# NFC.net
KiCad netlist of a schematic drawn in Altium Designer
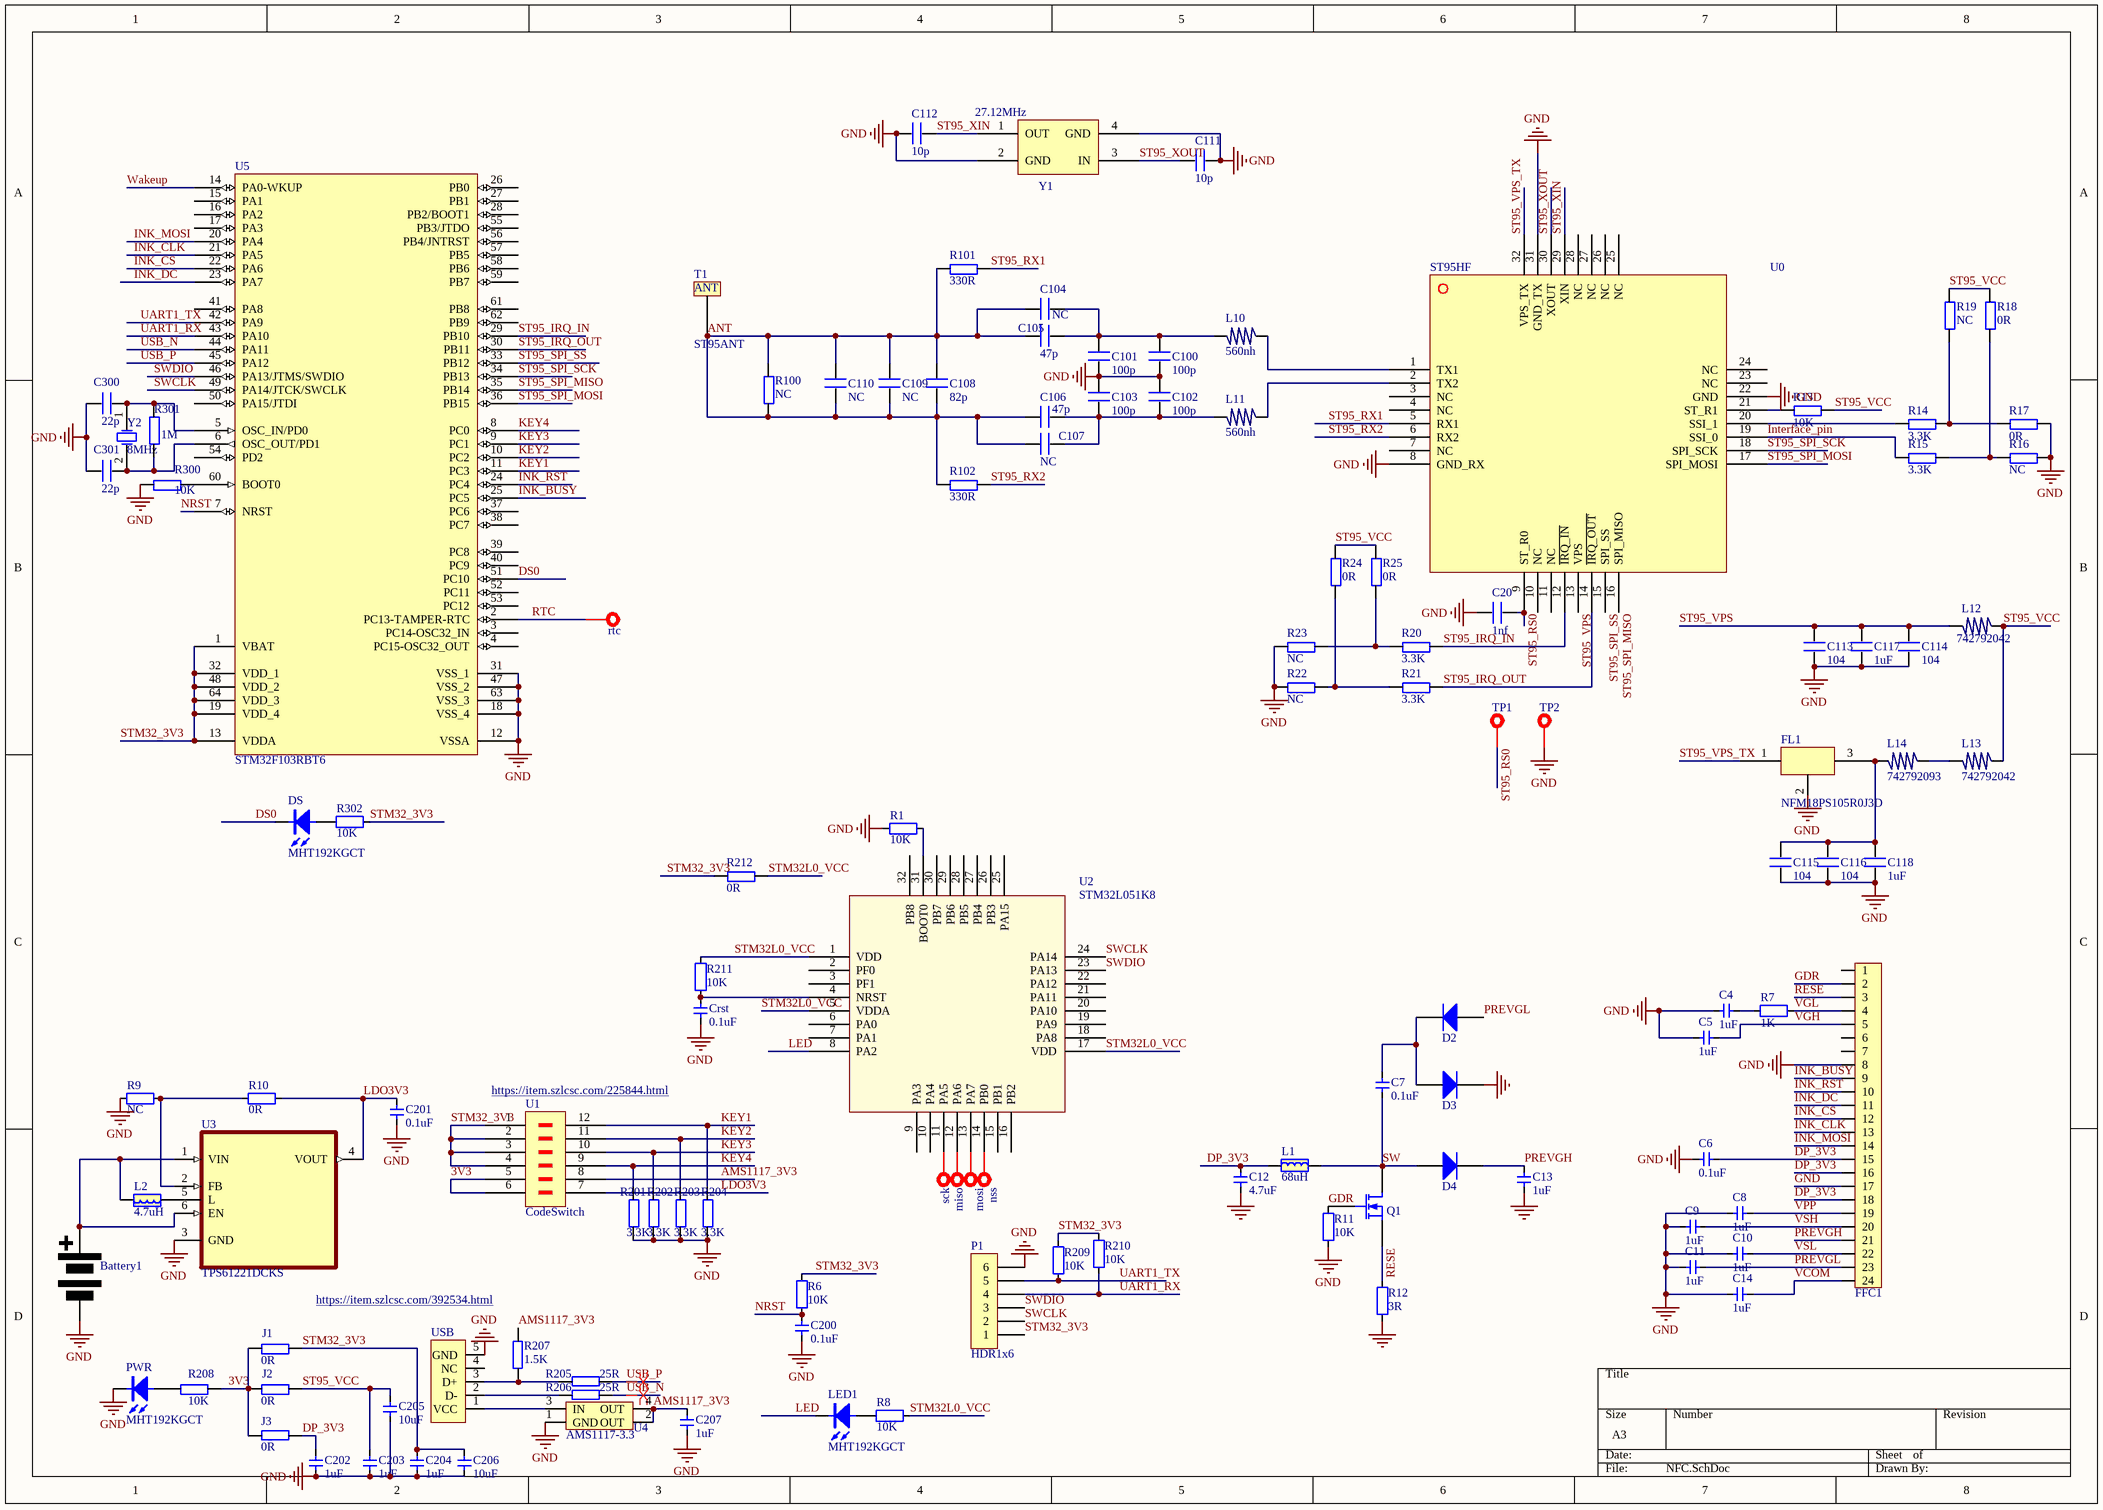
[diagram p0: NFC.SchDoc]

(export (version "E")
  (design (tool "Eeschema 10.0.6"))
  (components
    (comp (ref "Battery1")
      (value "Battery")
      (footprint "CR2032-1")
      (libsource (lib "KitSprout") (part "Battery"))
    )
    (comp (ref "C4")
      (value "1uF")
      (footprint "0402cap")
      (description "Capacitor")
      (libsource (lib "MyPcbLib") (part "电容-0402"))
    )
    (comp (ref "C5")
      (value "1uF")
      (footprint "0402cap")
      (description "Capacitor")
      (libsource (lib "MyPcbLib") (part "电容-0402"))
    )
    (comp (ref "C6")
      (value "0.1uF")
      (footprint "0402cap")
      (description "Capacitor")
      (libsource (lib "MyPcbLib") (part "电容-0402"))
    )
    (comp (ref "C7")
      (value "0.1uF")
      (footprint "0402cap")
      (description "Capacitor")
      (libsource (lib "MyPcbLib") (part "电容-0402"))
    )
    (comp (ref "C8")
      (value "1uF")
      (footprint "0402cap")
      (description "Capacitor")
      (libsource (lib "MyPcbLib") (part "电容-0402"))
    )
    (comp (ref "C9")
      (value "1uF")
      (footprint "0402cap")
      (description "Capacitor")
      (libsource (lib "MyPcbLib") (part "电容-0402"))
    )
    (comp (ref "C10")
      (value "1uF")
      (footprint "0402cap")
      (description "Capacitor")
      (libsource (lib "MyPcbLib") (part "电容-0402"))
    )
    (comp (ref "C11")
      (value "1uF")
      (footprint "0402cap")
      (description "Capacitor")
      (libsource (lib "MyPcbLib") (part "电容-0402"))
    )
    (comp (ref "C12")
      (value "4.7uF")
      (footprint "0402cap")
      (description "Capacitor")
      (libsource (lib "MyPcbLib") (part "电容-0603"))
    )
    (comp (ref "C13")
      (value "1uF")
      (footprint "0402cap")
      (description "Capacitor")
      (libsource (lib "MyPcbLib") (part "电容-0402"))
    )
    (comp (ref "C14")
      (value "1uF")
      (footprint "0402cap")
      (description "Capacitor")
      (libsource (lib "MyPcbLib") (part "电容-0402"))
    )
    (comp (ref "C20") (value "1nf") (footprint "0402cap") (libsource (lib "WARSHIP") (part "C")))
    (comp (ref "C100") (value "100p") (footprint "0603P") (libsource (lib "WARSHIP") (part "C")))
    (comp (ref "C101") (value "100p") (footprint "0603P") (libsource (lib "WARSHIP") (part "C")))
    (comp (ref "C102") (value "100p") (footprint "0603P") (libsource (lib "WARSHIP") (part "C")))
    (comp (ref "C103") (value "100p") (footprint "0603P") (libsource (lib "WARSHIP") (part "C")))
    (comp (ref "C104") (value "NC") (footprint "0603P") (libsource (lib "WARSHIP") (part "C")))
    (comp (ref "C105") (value "47p") (footprint "0603P") (libsource (lib "WARSHIP") (part "C")))
    (comp (ref "C106") (value "47p") (footprint "0603P") (libsource (lib "WARSHIP") (part "C")))
    (comp (ref "C107") (value "NC") (footprint "0603P") (libsource (lib "WARSHIP") (part "C")))
    (comp (ref "C108") (value "82p") (footprint "0603P") (libsource (lib "WARSHIP") (part "C")))
    (comp (ref "C109") (value "NC") (footprint "0603P") (libsource (lib "WARSHIP") (part "C")))
    (comp (ref "C110") (value "NC") (footprint "0603P") (libsource (lib "WARSHIP") (part "C")))
    (comp (ref "C111") (value "10p") (footprint "0402cap") (libsource (lib "WARSHIP") (part "C")))
    (comp (ref "C112") (value "10p") (footprint "0402cap") (libsource (lib "WARSHIP") (part "C")))
    (comp (ref "C113") (value "104") (footprint "0402cap") (libsource (lib "WARSHIP") (part "C")))
    (comp (ref "C114") (value "104") (footprint "0402cap") (libsource (lib "WARSHIP") (part "C")))
    (comp (ref "C115") (value "104") (footprint "0402cap") (libsource (lib "WARSHIP") (part "C")))
    (comp (ref "C116") (value "104") (footprint "0402cap") (libsource (lib "WARSHIP") (part "C")))
    (comp (ref "C117") (value "1uF") (footprint "0402cap") (libsource (lib "WARSHIP") (part "C")))
    (comp (ref "C118") (value "1uF") (footprint "0402cap") (libsource (lib "WARSHIP") (part "C")))
    (comp (ref "C200")
      (value "0.1uF")
      (footprint "0402cap")
      (description "Capacitor")
      (libsource (lib "MyPcbLib") (part "电容-0402"))
    )
    (comp (ref "C201")
      (value "0.1uF")
      (footprint "0402cap")
      (description "Capacitor")
      (libsource (lib "MyPcbLib") (part "电容-0402"))
    )
    (comp (ref "C202")
      (value "1uF")
      (footprint "0402cap")
      (description "Capacitor")
      (libsource (lib "MyPcbLib") (part "电容-0402"))
    )
    (comp (ref "C203")
      (value "1uF")
      (footprint "0402cap")
      (description "Capacitor")
      (libsource (lib "MyPcbLib") (part "电容-0402"))
    )
    (comp (ref "C204")
      (value "1uF")
      (footprint "0402cap")
      (description "Capacitor")
      (libsource (lib "MyPcbLib") (part "电容-0402"))
    )
    (comp (ref "C205")
      (value "10uF")
      (footprint "0603p")
      (description "Capacitor")
      (libsource (lib "MyPcbLib") (part "电容-0402"))
    )
    (comp (ref "C206")
      (value "10uF")
      (footprint "0603p")
      (description "Capacitor")
      (libsource (lib "MyPcbLib") (part "电容-0402"))
    )
    (comp (ref "C207")
      (value "1uF")
      (footprint "0402cap")
      (description "Capacitor")
      (libsource (lib "MyPcbLib") (part "电容-0402"))
    )
    (comp (ref "C300") (value "22p") (footprint "0402cap") (libsource (lib "WARSHIP") (part "C")))
    (comp (ref "C301") (value "22p") (footprint "0402cap") (libsource (lib "WARSHIP") (part "C")))
    (comp (ref "Crst")
      (value "0.1uF")
      (footprint "0402cap")
      (description "Capacitor")
      (libsource (lib "MyPcbLib") (part "电容-0402"))
    )
    (comp (ref "D2")
      (value "二极管-5819W")
      (footprint "SOD-123")
      (description "40V")
      (libsource (lib "MyPcbLib") (part "二极管-5819W"))
    )
    (comp (ref "D3")
      (value "二极管-5819W")
      (footprint "SOD-123")
      (description "40V")
      (libsource (lib "MyPcbLib") (part "二极管-5819W"))
    )
    (comp (ref "D4")
      (value "二极管-5819W")
      (footprint "SOD-123")
      (description "40V")
      (libsource (lib "MyPcbLib") (part "二极管-5819W"))
    )
    (comp (ref "DS")
      (value "MHT192KGCT")
      (footprint "LED-0603")
      (description "LED")
      (libsource (lib "General") (part "LED"))
    )
    (comp (ref "FFC1")
      (value "FFC_0.5_24")
      (footprint "FFC_0.5_24_INK")
      (description "FFC")
      (libsource (lib "MyPcbLib") (part "FFC_0.5_24_INK"))
    )
    (comp (ref "FL1")
      (value "NFM18PS105R0J3D")
      (footprint "NFM18PS")
      (libsource (lib "NFM18PS105R0J3D") (part "NFM18PS"))
    )
    (comp (ref "J1") (value "0R") (footprint "res0402") (libsource (lib "WARSHIP") (part "R")))
    (comp (ref "J2") (value "0R") (footprint "res0402") (libsource (lib "WARSHIP") (part "R")))
    (comp (ref "J3") (value "0R") (footprint "res0402") (libsource (lib "WARSHIP") (part "R")))
    (comp (ref "L1")
      (value "68uH")
      (footprint "2520-L")
      (description "磁珠")
      (libsource (lib "MyPcbLib") (part "电感-2520"))
    )
    (comp (ref "L2")
      (value "4.7uH")
      (footprint "0805-L")
      (description "磁珠")
      (libsource (lib "MyPcbLib") (part "电感-0805"))
    )
    (comp (ref "L10") (value "560nh") (footprint "0805") (libsource (lib "WARSHIP") (part "L")))
    (comp (ref "L11") (value "560nh") (footprint "0805") (libsource (lib "WARSHIP") (part "L")))
    (comp (ref "L12") (value "742792042") (footprint "0805") (libsource (lib "WARSHIP") (part "L")))
    (comp (ref "L13") (value "742792042") (footprint "0805") (libsource (lib "WARSHIP") (part "L")))
    (comp (ref "L14") (value "742792093") (footprint "0805") (libsource (lib "WARSHIP") (part "L")))
    (comp (ref "LED1")
      (value "MHT192KGCT")
      (footprint "LED-0603")
      (description "LED")
      (libsource (lib "General") (part "LED"))
    )
    (comp (ref "miso")
      (value "TestPoint")
      (footprint "TestPoint")
      (libsource (lib "TestPoint") (part "TestPoint"))
    )
    (comp (ref "mosi")
      (value "TestPoint")
      (footprint "TestPoint")
      (libsource (lib "TestPoint") (part "TestPoint"))
    )
    (comp (ref "nss")
      (value "TestPoint")
      (footprint "TestPoint")
      (libsource (lib "TestPoint") (part "TestPoint"))
    )
    (comp (ref "P1")
      (value "HDR1x6")
      (footprint "PIN-6-2.54-1.0")
      (description "Connector")
      (libsource (lib "General") (part "HDR1x6"))
    )
    (comp (ref "PWR")
      (value "MHT192KGCT")
      (footprint "LED-0603")
      (description "LED")
      (libsource (lib "General") (part "LED"))
    )
    (comp (ref "Q1")
      (value "MOSFET-N")
      (footprint "SOT23-3")
      (description "N-Channel MOSFET")
      (fields (field (name "PUBLISHER") "Altium Limited"))
      (libsource (lib "MyPcbLib") (part "MOSFET-N"))
    )
    (comp (ref "R1")
      (value "10K")
      (footprint "res0402")
      (description "Resistor")
      (libsource (lib "") (part "电阻-0402_2"))
    )
    (comp (ref "R6")
      (value "10K")
      (footprint "res0402")
      (description "Resistor")
      (libsource (lib "MyPcbLib") (part "电阻-0402"))
    )
    (comp (ref "R7")
      (value "1K")
      (footprint "res0402")
      (description "Resistor")
      (libsource (lib "") (part "电阻-0402_2"))
    )
    (comp (ref "R8")
      (value "10K")
      (footprint "res0402")
      (description "Resistor")
      (libsource (lib "") (part "电阻-0402_1"))
    )
    (comp (ref "R9")
      (value "NC")
      (footprint "res0402")
      (description "Resistor")
      (libsource (lib "") (part "电阻-0402_2"))
    )
    (comp (ref "R10")
      (value "0R")
      (footprint "res0402")
      (description "Resistor")
      (libsource (lib "") (part "电阻-0402_2"))
    )
    (comp (ref "R11")
      (value "10K")
      (footprint "res0402")
      (description "Resistor")
      (libsource (lib "MyPcbLib") (part "电阻-0402"))
    )
    (comp (ref "R12")
      (value "3R")
      (footprint "res0402")
      (description "Resistor")
      (libsource (lib "MyPcbLib") (part "电阻-0402"))
    )
    (comp (ref "R13") (value "10K") (footprint "res0402") (libsource (lib "WARSHIP") (part "R")))
    (comp (ref "R14") (value "3.3K") (footprint "res0402") (libsource (lib "WARSHIP") (part "R")))
    (comp (ref "R15") (value "3.3K") (footprint "res0402") (libsource (lib "WARSHIP") (part "R")))
    (comp (ref "R16") (value "NC") (footprint "res0402") (libsource (lib "WARSHIP") (part "R")))
    (comp (ref "R17") (value "0R") (footprint "res0402") (libsource (lib "WARSHIP") (part "R")))
    (comp (ref "R18") (value "0R") (footprint "res0402") (libsource (lib "WARSHIP") (part "R")))
    (comp (ref "R19") (value "NC") (footprint "res0402") (libsource (lib "WARSHIP") (part "R")))
    (comp (ref "R20") (value "3.3K") (footprint "res0402") (libsource (lib "WARSHIP") (part "R")))
    (comp (ref "R21") (value "3.3K") (footprint "res0402") (libsource (lib "WARSHIP") (part "R")))
    (comp (ref "R22") (value "NC") (footprint "res0402") (libsource (lib "WARSHIP") (part "R")))
    (comp (ref "R23") (value "NC") (footprint "res0402") (libsource (lib "WARSHIP") (part "R")))
    (comp (ref "R24") (value "0R") (footprint "res0402") (libsource (lib "WARSHIP") (part "R")))
    (comp (ref "R25") (value "0R") (footprint "res0402") (libsource (lib "WARSHIP") (part "R")))
    (comp (ref "R100") (value "NC") (footprint "0603R") (libsource (lib "WARSHIP") (part "R")))
    (comp (ref "R101") (value "330R") (footprint "0603R") (libsource (lib "WARSHIP") (part "R")))
    (comp (ref "R102") (value "330R") (footprint "0603R") (libsource (lib "WARSHIP") (part "R")))
    (comp (ref "R201") (value "3.3K") (footprint "res0402") (libsource (lib "WARSHIP") (part "R")))
    (comp (ref "R202") (value "3.3K") (footprint "res0402") (libsource (lib "WARSHIP") (part "R")))
    (comp (ref "R203") (value "3.3K") (footprint "res0402") (libsource (lib "WARSHIP") (part "R")))
    (comp (ref "R204") (value "3.3K") (footprint "res0402") (libsource (lib "WARSHIP") (part "R")))
    (comp (ref "R205") (value "25R") (footprint "res0402") (libsource (lib "WARSHIP") (part "R")))
    (comp (ref "R206") (value "25R") (footprint "res0402") (libsource (lib "WARSHIP") (part "R")))
    (comp (ref "R207") (value "1.5K") (footprint "res0402") (libsource (lib "WARSHIP") (part "R")))
    (comp (ref "R208") (value "10K") (footprint "res0402") (libsource (lib "WARSHIP") (part "R")))
    (comp (ref "R209")
      (value "10K")
      (footprint "res0402")
      (description "Resistor")
      (libsource (lib "MyPcbLib") (part "电阻-0402"))
    )
    (comp (ref "R210")
      (value "10K")
      (footprint "res0402")
      (description "Resistor")
      (libsource (lib "MyPcbLib") (part "电阻-0402"))
    )
    (comp (ref "R211")
      (value "10K")
      (footprint "res0402")
      (description "Resistor")
      (libsource (lib "MyPcbLib") (part "电阻-0402"))
    )
    (comp (ref "R212") (value "0R") (footprint "res0402") (libsource (lib "WARSHIP") (part "R")))
    (comp (ref "R300") (value "10K") (footprint "res0402") (libsource (lib "WARSHIP") (part "R")))
    (comp (ref "R301") (value "1M") (footprint "res0402") (libsource (lib "WARSHIP") (part "R")))
    (comp (ref "R302")
      (value "10K")
      (footprint "res0402")
      (description "Resistor")
      (libsource (lib "") (part "电阻-0402_1"))
    )
    (comp (ref "rtc")
      (value "TestPoint")
      (footprint "TestPoint")
      (libsource (lib "TestPoint") (part "TestPoint"))
    )
    (comp (ref "sck")
      (value "TestPoint")
      (footprint "TestPoint")
      (libsource (lib "TestPoint") (part "TestPoint"))
    )
    (comp (ref "T1") (value "ST95ANT") (footprint "ST95ANT") (libsource (lib "ST95ANT") (part "ST95ANT")))
    (comp (ref "TP1")
      (value "TestPoint")
      (footprint "TestPoint")
      (libsource (lib "TestPoint") (part "TestPoint"))
    )
    (comp (ref "TP2")
      (value "TestPoint")
      (footprint "TestPoint")
      (libsource (lib "TestPoint") (part "TestPoint"))
    )
    (comp (ref "U0")
      (value "ST95HF-VMD5T")
      (footprint "VFQFPN-32")
      (libsource (lib "ST95HF") (part "ST95HF"))
    )
    (comp (ref "U1")
      (value "CodeSwitch")
      (footprint "SOP12")
      (libsource (lib "CodeSwitch") (part "CodeSwitch"))
    )
    (comp (ref "U2")
      (value "STM32L051K8")
      (footprint "QFN-32")
      (libsource (lib "MyPcbLib") (part "STM32L051K8"))
    )
    (comp (ref "U3")
      (value "TPS61221DCKS")
      (footprint "SOT65P210X110-6N")
      (description "Boost Switching Regulator IC Positive Fixed 3.3V 1 Output 200mA _Switch_ 6-TSSOP, SC-88, SOT-363")
      (fields (field (name "MP") "TPS61221DCK") (field (name "MF") "Texas Instruments"))
      (libsource (lib "MyPcbLib") (part "TPS61221DCKT"))
    )
    (comp (ref "U4") (value "AMS1117-3.3") (footprint "SOT-223") (libsource (lib "WARSHIP") (part "AMS1117")))
    (comp (ref "U5")
      (value "STM32F103RBT6")
      (footprint "LQFP64_N")
      (description "STM32 ARM-based 32-bit MCU with 128 Kbytes Flash, 64-pin LQFP, Industrial Temperature")
      (fields (field (name "PUBLISHER") "*"))
      (libsource (lib "ST Microcontroller 32-Bit STM32 SCH") (part "STM32F103RBT6"))
    )
    (comp (ref "USB") (value "USB") (footprint "MICRO-USB") (libsource (lib "WARSHIP") (part "USB5")))
    (comp (ref "Y1") (value "27.12MHz") (footprint "SMD-2016_4P") (libsource (lib "NX2016") (part "NX2016")))
    (comp (ref "Y2")
      (value "8MHz")
      (footprint "XTAL_US")
      (description "Crystal Oscillator")
      (fields (field (name "PUBLISHER") "Altium Limited"))
      (libsource (lib "WARSHIP") (part "XTAL"))
    )
  )
  (nets
    (net (code "1") (name "/3V3") (class "Default")
      (node (ref "J1") (pin "1") (pintype "passive"))
      (node (ref "J2") (pin "1") (pintype "passive"))
      (node (ref "J3") (pin "2") (pintype "passive"))
      (node (ref "R208") (pin "2") (pintype "passive"))
      (node (ref "U1") (pin "5") (pintype "passive"))
      (node (ref "U1") (pin "6") (pintype "passive"))
    )
    (net (code "2") (name "/AMS1117_3V3") (class "Default")
      (node (ref "C207") (pin "1") (pinfunction "1_1") (pintype "passive"))
      (node (ref "R207") (pin "1") (pintype "passive"))
      (node (ref "U1") (pin "8") (pintype "passive"))
      (node (ref "U4") (pin "2") (pinfunction "OUT_2") (pintype "passive"))
      (node (ref "U4") (pin "4") (pinfunction "OUT_4") (pintype "passive"))
    )
    (net (code "3") (name "/ANT") (class "Default")
      (node (ref "C104") (pin "1") (pintype "passive"))
      (node (ref "C105") (pin "1") (pintype "passive"))
      (node (ref "C106") (pin "1") (pintype "passive"))
      (node (ref "C107") (pin "1") (pintype "passive"))
      (node (ref "C108") (pin "1") (pintype "passive"))
      (node (ref "C108") (pin "2") (pintype "passive"))
      (node (ref "C109") (pin "1") (pintype "passive"))
      (node (ref "C109") (pin "2") (pintype "passive"))
      (node (ref "C110") (pin "1") (pintype "passive"))
      (node (ref "C110") (pin "2") (pintype "passive"))
      (node (ref "R100") (pin "1") (pintype "passive"))
      (node (ref "R100") (pin "2") (pintype "passive"))
      (node (ref "R101") (pin "1") (pintype "passive"))
      (node (ref "R102") (pin "1") (pintype "passive"))
      (node (ref "T1") (pin "1") (pinfunction "ANT_1") (pintype "passive"))
    )
    (net (code "4") (name "/DP_3V3") (class "Default")
      (node (ref "C12") (pin "1") (pinfunction "1_1") (pintype "passive"))
      (node (ref "C202") (pin "1") (pinfunction "1_1") (pintype "passive"))
      (node (ref "C6") (pin "2") (pinfunction "2_2") (pintype "passive"))
      (node (ref "FFC1") (pin "15") (pinfunction "15_15") (pintype "passive"))
      (node (ref "FFC1") (pin "16") (pinfunction "16_16") (pintype "passive"))
      (node (ref "FFC1") (pin "18") (pinfunction "18_18") (pintype "passive"))
      (node (ref "J3") (pin "1") (pintype "passive"))
      (node (ref "L1") (pin "1") (pintype "passive"))
    )
    (net (code "5") (name "/DS0") (class "Default")
      (node (ref "DS") (pin "2") (pinfunction "C_2") (pintype "passive"))
      (node (ref "U5") (pin "51") (pinfunction "PC10_51") (pintype "bidirectional"))
    )
    (net (code "6") (name "/GDR") (class "Default")
      (node (ref "FFC1") (pin "2") (pinfunction "2_2") (pintype "passive"))
      (node (ref "Q1") (pin "1") (pinfunction "G_1") (pintype "passive"))
      (node (ref "R11") (pin "2") (pinfunction "2_2") (pintype "passive"))
    )
    (net (code "7") (name "/INK_BUSY") (class "Default")
      (node (ref "FFC1") (pin "9") (pinfunction "9_9") (pintype "passive"))
      (node (ref "U5") (pin "25") (pinfunction "PC5_25") (pintype "bidirectional"))
    )
    (net (code "8") (name "/INK_CLK") (class "Default")
      (node (ref "FFC1") (pin "13") (pinfunction "13_13") (pintype "passive"))
      (node (ref "U5") (pin "21") (pinfunction "PA5_21") (pintype "bidirectional"))
    )
    (net (code "9") (name "/INK_CS") (class "Default")
      (node (ref "FFC1") (pin "12") (pinfunction "12_12") (pintype "passive"))
      (node (ref "U5") (pin "22") (pinfunction "PA6_22") (pintype "bidirectional"))
    )
    (net (code "10") (name "/INK_DC") (class "Default")
      (node (ref "FFC1") (pin "11") (pinfunction "11_11") (pintype "passive"))
      (node (ref "U5") (pin "23") (pinfunction "PA7_23") (pintype "bidirectional"))
    )
    (net (code "11") (name "/INK_MOSI") (class "Default")
      (node (ref "FFC1") (pin "14") (pinfunction "14_14") (pintype "passive"))
      (node (ref "U5") (pin "20") (pinfunction "PA4_20") (pintype "bidirectional"))
    )
    (net (code "12") (name "/INK_RST") (class "Default")
      (node (ref "FFC1") (pin "10") (pinfunction "10_10") (pintype "passive"))
      (node (ref "U5") (pin "24") (pinfunction "PC4_24") (pintype "bidirectional"))
    )
    (net (code "13") (name "/Interface_pin") (class "Default")
      (node (ref "R15") (pin "1") (pintype "passive"))
      (node (ref "U0") (pin "19") (pinfunction "SSI_0_19") (pintype "passive"))
    )
    (net (code "14") (name "/KEY1") (class "Default")
      (node (ref "R204") (pin "2") (pintype "passive"))
      (node (ref "U1") (pin "12") (pintype "passive"))
      (node (ref "U5") (pin "11") (pinfunction "PC3_11") (pintype "bidirectional"))
    )
    (net (code "15") (name "/KEY2") (class "Default")
      (node (ref "R203") (pin "2") (pintype "passive"))
      (node (ref "U1") (pin "11") (pintype "passive"))
      (node (ref "U5") (pin "10") (pinfunction "PC2_10") (pintype "bidirectional"))
    )
    (net (code "16") (name "/KEY3") (class "Default")
      (node (ref "R202") (pin "2") (pintype "passive"))
      (node (ref "U1") (pin "10") (pintype "passive"))
      (node (ref "U5") (pin "9") (pinfunction "PC1_9") (pintype "bidirectional"))
    )
    (net (code "17") (name "/KEY4") (class "Default")
      (node (ref "R201") (pin "2") (pintype "passive"))
      (node (ref "U1") (pin "9") (pintype "passive"))
      (node (ref "U5") (pin "8") (pinfunction "PC0_8") (pintype "bidirectional"))
    )
    (net (code "18") (name "/LDO3V3") (class "Default")
      (node (ref "C201") (pin "1") (pinfunction "1_1") (pintype "passive"))
      (node (ref "R10") (pin "1") (pinfunction "1_1") (pintype "passive"))
      (node (ref "U1") (pin "7") (pintype "passive"))
      (node (ref "U3") (pin "4") (pinfunction "VOUT_4") (pintype "output"))
    )
    (net (code "19") (name "/LED") (class "Default")
      (node (ref "LED1") (pin "2") (pinfunction "C_2") (pintype "passive"))
      (node (ref "U2") (pin "8") (pinfunction "PA2_8") (pintype "passive"))
    )
    (net (code "20") (name "/NRST") (class "Default")
      (node (ref "C200") (pin "1") (pinfunction "1_1") (pintype "passive"))
      (node (ref "R6") (pin "1") (pinfunction "1_1") (pintype "passive"))
      (node (ref "U5") (pin "7") (pinfunction "NRST_7") (pintype "bidirectional"))
    )
    (net (code "21") (name "/PREVGH") (class "Default")
      (node (ref "C13") (pin "1") (pinfunction "1_1") (pintype "passive"))
      (node (ref "D4") (pin "2") (pinfunction "K_2") (pintype "passive"))
      (node (ref "FFC1") (pin "21") (pinfunction "21_21") (pintype "passive"))
    )
    (net (code "22") (name "/PREVGL") (class "Default")
      (node (ref "C11") (pin "2") (pinfunction "2_2") (pintype "passive"))
      (node (ref "D2") (pin "1") (pinfunction "A_1") (pintype "passive"))
      (node (ref "FFC1") (pin "23") (pinfunction "23_23") (pintype "passive"))
    )
    (net (code "23") (name "/RESE") (class "Default")
      (node (ref "FFC1") (pin "3") (pinfunction "3_3") (pintype "passive"))
      (node (ref "Q1") (pin "2") (pinfunction "S_2") (pintype "passive"))
      (node (ref "R12") (pin "2") (pinfunction "2_2") (pintype "passive"))
    )
    (net (code "24") (name "/RTC") (class "Default")
      (node (ref "U5") (pin "2") (pinfunction "PC13-TAMPER-RTC_2") (pintype "bidirectional"))
      (node (ref "rtc") (pin "1") (pinfunction "TP_1") (pintype "passive"))
    )
    (net (code "25") (name "/ST95_IRQ_IN") (class "Default")
      (node (ref "R20") (pin "2") (pintype "passive"))
      (node (ref "U0") (pin "12") (pinfunction "~{IRQ_IN}_12") (pintype "passive"))
      (node (ref "U5") (pin "29") (pinfunction "PB10_29") (pintype "bidirectional"))
    )
    (net (code "26") (name "/ST95_IRQ_OUT") (class "Default")
      (node (ref "R21") (pin "2") (pintype "passive"))
      (node (ref "U0") (pin "14") (pinfunction "~{IRQ_OUT}_14") (pintype "passive"))
      (node (ref "U5") (pin "30") (pinfunction "PB11_30") (pintype "bidirectional"))
    )
    (net (code "27") (name "/ST95_RS0") (class "Default")
      (node (ref "C20") (pin "1") (pintype "passive"))
      (node (ref "TP1") (pin "1") (pinfunction "TP_1") (pintype "passive"))
      (node (ref "U0") (pin "9") (pinfunction "ST_R0_9") (pintype "passive"))
    )
    (net (code "28") (name "/ST95_RX1") (class "Default")
      (node (ref "R101") (pin "2") (pintype "passive"))
      (node (ref "U0") (pin "5") (pinfunction "RX1_5") (pintype "passive"))
    )
    (net (code "29") (name "/ST95_RX2") (class "Default")
      (node (ref "R102") (pin "2") (pintype "passive"))
      (node (ref "U0") (pin "6") (pinfunction "RX2_6") (pintype "passive"))
    )
    (net (code "30") (name "/ST95_SPI_MISO") (class "Default")
      (node (ref "U0") (pin "16") (pinfunction "SPI_MISO_16") (pintype "passive"))
      (node (ref "U5") (pin "35") (pinfunction "PB14_35") (pintype "bidirectional"))
    )
    (net (code "31") (name "/ST95_SPI_MOSI") (class "Default")
      (node (ref "U0") (pin "17") (pinfunction "SPI_MOSI_17") (pintype "passive"))
      (node (ref "U5") (pin "36") (pinfunction "PB15_36") (pintype "bidirectional"))
    )
    (net (code "32") (name "/ST95_SPI_SCK") (class "Default")
      (node (ref "U0") (pin "18") (pinfunction "SPI_SCK_18") (pintype "passive"))
      (node (ref "U5") (pin "34") (pinfunction "PB13_34") (pintype "bidirectional"))
    )
    (net (code "33") (name "/ST95_SPI_SS") (class "Default")
      (node (ref "U0") (pin "15") (pinfunction "SPI_SS_15") (pintype "passive"))
      (node (ref "U5") (pin "33") (pinfunction "PB12_33") (pintype "bidirectional"))
    )
    (net (code "34") (name "/ST95_VCC") (class "Default")
      (node (ref "C203") (pin "1") (pinfunction "1_1") (pintype "passive"))
      (node (ref "C205") (pin "1") (pinfunction "1_1") (pintype "passive"))
      (node (ref "J2") (pin "2") (pintype "passive"))
      (node (ref "L12") (pin "1") (pintype "passive"))
      (node (ref "L13") (pin "1") (pintype "passive"))
      (node (ref "R13") (pin "2") (pintype "passive"))
      (node (ref "R18") (pin "2") (pintype "passive"))
      (node (ref "R19") (pin "2") (pintype "passive"))
      (node (ref "R24") (pin "2") (pintype "passive"))
      (node (ref "R25") (pin "2") (pintype "passive"))
    )
    (net (code "35") (name "/ST95_VPS") (class "Default")
      (node (ref "C113") (pin "1") (pintype "passive"))
      (node (ref "C114") (pin "1") (pintype "passive"))
      (node (ref "C117") (pin "2") (pintype "passive"))
      (node (ref "L12") (pin "2") (pintype "passive"))
      (node (ref "U0") (pin "13") (pinfunction "VPS_13") (pintype "passive"))
    )
    (net (code "36") (name "/ST95_VPS_TX") (class "Default")
      (node (ref "FL1") (pin "1") (pinfunction "1_1") (pintype "passive"))
      (node (ref "U0") (pin "32") (pinfunction "VPS_TX_32") (pintype "passive"))
    )
    (net (code "37") (name "/ST95_XIN") (class "Default")
      (node (ref "C112") (pin "2") (pintype "passive"))
      (node (ref "U0") (pin "29") (pinfunction "XIN_29") (pintype "passive"))
      (node (ref "Y1") (pin "1") (pinfunction "OUT_1") (pintype "passive"))
    )
    (net (code "38") (name "/ST95_XOUT") (class "Default")
      (node (ref "C111") (pin "1") (pintype "passive"))
      (node (ref "U0") (pin "30") (pinfunction "XOUT_30") (pintype "passive"))
      (node (ref "Y1") (pin "3") (pinfunction "IN_3") (pintype "passive"))
    )
    (net (code "39") (name "/STM32L0_VCC") (class "Default")
      (node (ref "R211") (pin "2") (pinfunction "2_2") (pintype "passive"))
      (node (ref "R212") (pin "2") (pintype "passive"))
      (node (ref "R8") (pin "2") (pinfunction "2_2") (pintype "passive"))
      (node (ref "U2") (pin "1") (pinfunction "VDD_1") (pintype "passive"))
      (node (ref "U2") (pin "17") (pinfunction "VDD_17") (pintype "passive"))
      (node (ref "U2") (pin "5") (pinfunction "VDDA_5") (pintype "passive"))
    )
    (net (code "40") (name "/STM32_3V3") (class "Default")
      (node (ref "C204") (pin "1") (pinfunction "1_1") (pintype "passive"))
      (node (ref "C206") (pin "1") (pinfunction "1_1") (pintype "passive"))
      (node (ref "J1") (pin "2") (pintype "passive"))
      (node (ref "P1") (pin "1") (pinfunction "1_1") (pintype "passive"))
      (node (ref "R209") (pin "2") (pinfunction "2_2") (pintype "passive"))
      (node (ref "R210") (pin "2") (pinfunction "2_2") (pintype "passive"))
      (node (ref "R212") (pin "1") (pintype "passive"))
      (node (ref "R302") (pin "2") (pinfunction "2_2") (pintype "passive"))
      (node (ref "R6") (pin "2") (pinfunction "2_2") (pintype "passive"))
      (node (ref "U1") (pin "1") (pintype "passive"))
      (node (ref "U1") (pin "2") (pintype "passive"))
      (node (ref "U1") (pin "3") (pintype "passive"))
      (node (ref "U1") (pin "4") (pintype "passive"))
      (node (ref "U5") (pin "1") (pinfunction "VBAT_1") (pintype "power_in"))
      (node (ref "U5") (pin "13") (pinfunction "VDDA_13") (pintype "power_in"))
      (node (ref "U5") (pin "19") (pinfunction "VDD_4_19") (pintype "power_in"))
      (node (ref "U5") (pin "32") (pinfunction "VDD_1_32") (pintype "power_in"))
      (node (ref "U5") (pin "48") (pinfunction "VDD_2_48") (pintype "power_in"))
      (node (ref "U5") (pin "64") (pinfunction "VDD_3_64") (pintype "power_in"))
    )
    (net (code "41") (name "/SW") (class "Default")
      (node (ref "C7") (pin "2") (pinfunction "2_2") (pintype "passive"))
      (node (ref "D4") (pin "1") (pinfunction "A_1") (pintype "passive"))
      (node (ref "L1") (pin "2") (pinfunction "2_2") (pintype "passive"))
      (node (ref "Q1") (pin "3") (pinfunction "D_3") (pintype "passive"))
    )
    (net (code "42") (name "/SWCLK") (class "Default")
      (node (ref "P1") (pin "2") (pinfunction "2_2") (pintype "passive"))
      (node (ref "U2") (pin "24") (pinfunction "PA14_24") (pintype "passive"))
      (node (ref "U5") (pin "49") (pinfunction "PA14/JTCK/SWCLK_49") (pintype "bidirectional"))
    )
    (net (code "43") (name "/SWDIO") (class "Default")
      (node (ref "P1") (pin "3") (pinfunction "3_3") (pintype "passive"))
      (node (ref "U2") (pin "23") (pinfunction "PA13_23") (pintype "passive"))
      (node (ref "U5") (pin "46") (pinfunction "PA13/JTMS/SWDIO_46") (pintype "bidirectional"))
    )
    (net (code "44") (name "/UART1_RX") (class "Default")
      (node (ref "P1") (pin "4") (pinfunction "4_4") (pintype "passive"))
      (node (ref "R210") (pin "1") (pinfunction "1_1") (pintype "passive"))
      (node (ref "U5") (pin "43") (pinfunction "PA10_43") (pintype "bidirectional"))
    )
    (net (code "45") (name "/UART1_TX") (class "Default")
      (node (ref "P1") (pin "5") (pinfunction "5_5") (pintype "passive"))
      (node (ref "R209") (pin "1") (pinfunction "1_1") (pintype "passive"))
      (node (ref "U5") (pin "42") (pinfunction "PA9_42") (pintype "bidirectional"))
    )
    (net (code "46") (name "/USB_N") (class "Default")
      (node (ref "R206") (pin "1") (pintype "passive"))
      (node (ref "U5") (pin "44") (pinfunction "PA11_44") (pintype "bidirectional"))
    )
    (net (code "47") (name "/USB_P") (class "Default")
      (node (ref "R205") (pin "1") (pintype "passive"))
      (node (ref "U5") (pin "45") (pinfunction "PA12_45") (pintype "bidirectional"))
    )
    (net (code "48") (name "/VCOM") (class "Default")
      (node (ref "C14") (pin "2") (pinfunction "2_2") (pintype "passive"))
      (node (ref "FFC1") (pin "24") (pinfunction "24_24") (pintype "passive"))
    )
    (net (code "49") (name "/VGH") (class "Default")
      (node (ref "C5") (pin "2") (pinfunction "2_2") (pintype "passive"))
      (node (ref "FFC1") (pin "5") (pinfunction "5_5") (pintype "passive"))
    )
    (net (code "50") (name "/VGL") (class "Default")
      (node (ref "FFC1") (pin "4") (pinfunction "4_4") (pintype "passive"))
      (node (ref "R7") (pin "1") (pinfunction "1_1") (pintype "passive"))
    )
    (net (code "51") (name "/VPP") (class "Default")
      (node (ref "C8") (pin "2") (pinfunction "2_2") (pintype "passive"))
      (node (ref "FFC1") (pin "19") (pinfunction "19_19") (pintype "passive"))
    )
    (net (code "52") (name "/VSH") (class "Default")
      (node (ref "C9") (pin "2") (pinfunction "2_2") (pintype "passive"))
      (node (ref "FFC1") (pin "20") (pinfunction "20_20") (pintype "passive"))
    )
    (net (code "53") (name "/VSL") (class "Default")
      (node (ref "C10") (pin "2") (pinfunction "2_2") (pintype "passive"))
      (node (ref "FFC1") (pin "22") (pinfunction "22_22") (pintype "passive"))
    )
    (net (code "54") (name "/Wakeup") (class "Default")
      (node (ref "U5") (pin "14") (pinfunction "PA0-WKUP_14") (pintype "bidirectional"))
    )
    (net (code "55") (name "GND") (class "Default")
      (node (ref "Battery1") (pin "1") (pinfunction "-_1") (pintype "passive"))
      (node (ref "C10") (pin "1") (pinfunction "1_1") (pintype "passive"))
      (node (ref "C100") (pin "1") (pintype "passive"))
      (node (ref "C101") (pin "1") (pintype "passive"))
      (node (ref "C102") (pin "2") (pintype "passive"))
      (node (ref "C103") (pin "2") (pintype "passive"))
      (node (ref "C11") (pin "1") (pinfunction "1_1") (pintype "passive"))
      (node (ref "C111") (pin "2") (pintype "passive"))
      (node (ref "C112") (pin "1") (pintype "passive"))
      (node (ref "C113") (pin "2") (pintype "passive"))
      (node (ref "C114") (pin "2") (pintype "passive"))
      (node (ref "C115") (pin "1") (pintype "passive"))
      (node (ref "C116") (pin "1") (pintype "passive"))
      (node (ref "C117") (pin "1") (pintype "passive"))
      (node (ref "C118") (pin "1") (pintype "passive"))
      (node (ref "C12") (pin "2") (pinfunction "2_2") (pintype "passive"))
      (node (ref "C13") (pin "2") (pinfunction "2_2") (pintype "passive"))
      (node (ref "C14") (pin "1") (pinfunction "1_1") (pintype "passive"))
      (node (ref "C20") (pin "2") (pintype "passive"))
      (node (ref "C200") (pin "2") (pinfunction "2_2") (pintype "passive"))
      (node (ref "C201") (pin "2") (pinfunction "2_2") (pintype "passive"))
      (node (ref "C202") (pin "2") (pinfunction "2_2") (pintype "passive"))
      (node (ref "C203") (pin "2") (pinfunction "2_2") (pintype "passive"))
      (node (ref "C204") (pin "2") (pinfunction "2_2") (pintype "passive"))
      (node (ref "C205") (pin "2") (pinfunction "2_2") (pintype "passive"))
      (node (ref "C206") (pin "2") (pinfunction "2_2") (pintype "passive"))
      (node (ref "C207") (pin "2") (pinfunction "2_2") (pintype "passive"))
      (node (ref "C300") (pin "1") (pintype "passive"))
      (node (ref "C301") (pin "1") (pintype "passive"))
      (node (ref "C4") (pin "1") (pinfunction "1_1") (pintype "passive"))
      (node (ref "C5") (pin "1") (pinfunction "1_1") (pintype "passive"))
      (node (ref "C6") (pin "1") (pinfunction "1_1") (pintype "passive"))
      (node (ref "C8") (pin "1") (pinfunction "1_1") (pintype "passive"))
      (node (ref "C9") (pin "1") (pinfunction "1_1") (pintype "passive"))
      (node (ref "Crst") (pin "2") (pinfunction "2_2") (pintype "passive"))
      (node (ref "D3") (pin "2") (pinfunction "K_2") (pintype "passive"))
      (node (ref "FFC1") (pin "17") (pinfunction "17_17") (pintype "passive"))
      (node (ref "FFC1") (pin "8") (pinfunction "8_8") (pintype "passive"))
      (node (ref "FL1") (pin "2") (pinfunction "2_2") (pintype "passive"))
      (node (ref "P1") (pin "6") (pinfunction "6_6") (pintype "passive"))
      (node (ref "PWR") (pin "2") (pinfunction "C_2") (pintype "passive"))
      (node (ref "R1") (pin "2") (pinfunction "2_2") (pintype "passive"))
      (node (ref "R11") (pin "1") (pinfunction "1_1") (pintype "passive"))
      (node (ref "R12") (pin "1") (pinfunction "1_1") (pintype "passive"))
      (node (ref "R16") (pin "2") (pintype "passive"))
      (node (ref "R17") (pin "2") (pintype "passive"))
      (node (ref "R201") (pin "1") (pintype "passive"))
      (node (ref "R202") (pin "1") (pintype "passive"))
      (node (ref "R203") (pin "1") (pintype "passive"))
      (node (ref "R204") (pin "1") (pintype "passive"))
      (node (ref "R22") (pin "1") (pintype "passive"))
      (node (ref "R23") (pin "1") (pintype "passive"))
      (node (ref "R300") (pin "1") (pintype "passive"))
      (node (ref "R9") (pin "2") (pinfunction "2_2") (pintype "passive"))
      (node (ref "TP2") (pin "1") (pinfunction "TP_1") (pintype "passive"))
      (node (ref "U0") (pin "22") (pinfunction "GND_22") (pintype "passive"))
      (node (ref "U0") (pin "31") (pinfunction "GND_TX_31") (pintype "passive"))
      (node (ref "U0") (pin "8") (pinfunction "GND_RX_8") (pintype "passive"))
      (node (ref "U3") (pin "3") (pinfunction "GND_3") (pintype "passive"))
      (node (ref "U4") (pin "1") (pinfunction "GND_1") (pintype "passive"))
      (node (ref "U5") (pin "12") (pinfunction "VSSA_12") (pintype "power_in"))
      (node (ref "U5") (pin "18") (pinfunction "VSS_4_18") (pintype "power_in"))
      (node (ref "U5") (pin "31") (pinfunction "VSS_1_31") (pintype "power_in"))
      (node (ref "U5") (pin "47") (pinfunction "VSS_2_47") (pintype "power_in"))
      (node (ref "U5") (pin "63") (pinfunction "VSS_3_63") (pintype "power_in"))
      (node (ref "USB") (pin "5") (pinfunction "GND_5") (pintype "passive"))
      (node (ref "Y1") (pin "2") (pinfunction "GND_2") (pintype "passive"))
      (node (ref "Y1") (pin "4") (pinfunction "GND_4") (pintype "passive"))
    )
    (net (code "56") (name "Net-(Battery1-+)") (class "Default")
      (node (ref "Battery1") (pin "2") (pinfunction "+_2") (pintype "passive"))
      (node (ref "L2") (pin "2") (pinfunction "2_2") (pintype "passive"))
      (node (ref "U3") (pin "1") (pinfunction "VIN_1") (pintype "input"))
      (node (ref "U3") (pin "6") (pinfunction "EN_6") (pintype "input"))
    )
    (net (code "57") (name "Net-(C4-Pad2)") (class "Default")
      (node (ref "C4") (pin "2") (pinfunction "2_2") (pintype "passive"))
      (node (ref "R7") (pin "2") (pinfunction "2_2") (pintype "passive"))
    )
    (net (code "58") (name "Net-(C100-Pad2)") (class "Default")
      (node (ref "C100") (pin "2") (pintype "passive"))
      (node (ref "C101") (pin "2") (pintype "passive"))
      (node (ref "C104") (pin "2") (pintype "passive"))
      (node (ref "C105") (pin "2") (pintype "passive"))
      (node (ref "L10") (pin "2") (pintype "passive"))
    )
    (net (code "59") (name "Net-(C102-Pad1)") (class "Default")
      (node (ref "C102") (pin "1") (pintype "passive"))
      (node (ref "C103") (pin "1") (pintype "passive"))
      (node (ref "C106") (pin "2") (pintype "passive"))
      (node (ref "C107") (pin "2") (pintype "passive"))
      (node (ref "L11") (pin "2") (pintype "passive"))
    )
    (net (code "60") (name "Net-(C115-Pad2)") (class "Default")
      (node (ref "C115") (pin "2") (pintype "passive"))
      (node (ref "C116") (pin "2") (pintype "passive"))
      (node (ref "C118") (pin "2") (pintype "passive"))
      (node (ref "FL1") (pin "3") (pinfunction "3_3") (pintype "passive"))
      (node (ref "L14") (pin "2") (pintype "passive"))
    )
    (net (code "61") (name "Net-(D2-K)") (class "Default")
      (node (ref "C7") (pin "1") (pinfunction "1_1") (pintype "passive"))
      (node (ref "D2") (pin "2") (pinfunction "K_2") (pintype "passive"))
      (node (ref "D3") (pin "1") (pinfunction "A_1") (pintype "passive"))
    )
    (net (code "62") (name "Net-(DS-A)") (class "Default")
      (node (ref "DS") (pin "1") (pinfunction "A_1") (pintype "passive"))
      (node (ref "R302") (pin "1") (pinfunction "1_1") (pintype "passive"))
    )
    (net (code "63") (name "Net-(L13-Pad2)") (class "Default")
      (node (ref "L13") (pin "2") (pintype "passive"))
      (node (ref "L14") (pin "1") (pintype "passive"))
    )
    (net (code "64") (name "Net-(LED1-A)") (class "Default")
      (node (ref "LED1") (pin "1") (pinfunction "A_1") (pintype "passive"))
      (node (ref "R8") (pin "1") (pinfunction "1_1") (pintype "passive"))
    )
    (net (code "65") (name "Net-(PWR-A)") (class "Default")
      (node (ref "PWR") (pin "1") (pinfunction "A_1") (pintype "passive"))
      (node (ref "R208") (pin "1") (pintype "passive"))
    )
    (net (code "66") (name "Net-(R14-Pad2)") (class "Default")
      (node (ref "R14") (pin "2") (pintype "passive"))
      (node (ref "R17") (pin "1") (pintype "passive"))
      (node (ref "R19") (pin "1") (pintype "passive"))
    )
    (net (code "67") (name "Net-(R15-Pad2)") (class "Default")
      (node (ref "R15") (pin "2") (pintype "passive"))
      (node (ref "R16") (pin "1") (pintype "passive"))
      (node (ref "R18") (pin "1") (pintype "passive"))
    )
    (net (code "68") (name "Net-(R20-Pad1)") (class "Default")
      (node (ref "R20") (pin "1") (pintype "passive"))
      (node (ref "R23") (pin "2") (pintype "passive"))
      (node (ref "R25") (pin "1") (pintype "passive"))
    )
    (net (code "69") (name "Net-(R21-Pad1)") (class "Default")
      (node (ref "R21") (pin "1") (pintype "passive"))
      (node (ref "R22") (pin "2") (pintype "passive"))
      (node (ref "R24") (pin "1") (pintype "passive"))
    )
    (net (code "70") (name "Net-(U0-SSI_1)") (class "Default")
      (node (ref "R14") (pin "1") (pintype "passive"))
      (node (ref "U0") (pin "20") (pinfunction "SSI_1_20") (pintype "passive"))
    )
    (net (code "71") (name "Net-(U0-ST_R1)") (class "Default")
      (node (ref "R13") (pin "1") (pintype "passive"))
      (node (ref "U0") (pin "21") (pinfunction "ST_R1_21") (pintype "passive"))
    )
    (net (code "72") (name "Net-(U0-TX1)") (class "Default")
      (node (ref "L10") (pin "1") (pintype "passive"))
      (node (ref "U0") (pin "1") (pinfunction "TX1_1") (pintype "passive"))
    )
    (net (code "73") (name "Net-(U0-TX2)") (class "Default")
      (node (ref "L11") (pin "1") (pintype "passive"))
      (node (ref "U0") (pin "2") (pinfunction "TX2_2") (pintype "passive"))
    )
    (net (code "74") (name "Net-(U2-BOOT0)") (class "Default")
      (node (ref "R1") (pin "1") (pinfunction "1_1") (pintype "passive"))
      (node (ref "U2") (pin "31") (pinfunction "BOOT0_31") (pintype "passive"))
    )
    (net (code "75") (name "Net-(U2-NRST)") (class "Default")
      (node (ref "Crst") (pin "1") (pinfunction "1_1") (pintype "passive"))
      (node (ref "R211") (pin "1") (pinfunction "1_1") (pintype "passive"))
      (node (ref "U2") (pin "4") (pinfunction "NRST_4") (pintype "passive"))
    )
    (net (code "76") (name "Net-(U2-PA5)") (class "Default")
      (node (ref "U2") (pin "11") (pinfunction "PA5_11") (pintype "passive"))
      (node (ref "sck") (pin "1") (pinfunction "TP_1") (pintype "passive"))
    )
    (net (code "77") (name "Net-(U2-PA6)") (class "Default")
      (node (ref "U2") (pin "12") (pinfunction "PA6_12") (pintype "passive"))
      (node (ref "miso") (pin "1") (pinfunction "TP_1") (pintype "passive"))
    )
    (net (code "78") (name "Net-(U2-PA7)") (class "Default")
      (node (ref "U2") (pin "13") (pinfunction "PA7_13") (pintype "passive"))
      (node (ref "mosi") (pin "1") (pinfunction "TP_1") (pintype "passive"))
    )
    (net (code "79") (name "Net-(U2-PB0)") (class "Default")
      (node (ref "U2") (pin "14") (pinfunction "PB0_14") (pintype "passive"))
      (node (ref "nss") (pin "1") (pinfunction "TP_1") (pintype "passive"))
    )
    (net (code "80") (name "Net-(U3-FB)") (class "Default")
      (node (ref "R10") (pin "2") (pinfunction "2_2") (pintype "passive"))
      (node (ref "R9") (pin "1") (pinfunction "1_1") (pintype "passive"))
      (node (ref "U3") (pin "2") (pinfunction "FB_2") (pintype "input"))
    )
    (net (code "81") (name "Net-(U3-L)") (class "Default")
      (node (ref "L2") (pin "1") (pintype "passive"))
      (node (ref "U3") (pin "5") (pinfunction "L_5") (pintype "passive"))
    )
    (net (code "82") (name "Net-(U4-IN)") (class "Default")
      (node (ref "U4") (pin "3") (pinfunction "IN_3") (pintype "passive"))
      (node (ref "USB") (pin "1") (pinfunction "VCC_1") (pintype "passive"))
    )
    (net (code "83") (name "Net-(U5-BOOT0)") (class "Default")
      (node (ref "R300") (pin "2") (pintype "passive"))
      (node (ref "U5") (pin "60") (pinfunction "BOOT0_60") (pintype "input"))
    )
    (net (code "84") (name "Net-(U5-OSC_IN{slash}PD0)") (class "Default")
      (node (ref "C300") (pin "2") (pintype "passive"))
      (node (ref "R301") (pin "2") (pintype "passive"))
      (node (ref "U5") (pin "5") (pinfunction "OSC_IN/PD0_5") (pintype "input"))
      (node (ref "Y2") (pin "1") (pinfunction "OSC1_1") (pintype "passive"))
    )
    (net (code "85") (name "Net-(U5-OSC_OUT{slash}PD1)") (class "Default")
      (node (ref "C301") (pin "2") (pintype "passive"))
      (node (ref "R301") (pin "1") (pintype "passive"))
      (node (ref "U5") (pin "6") (pinfunction "OSC_OUT/PD1_6") (pintype "output"))
      (node (ref "Y2") (pin "2") (pinfunction "OSC2_2") (pintype "passive"))
    )
    (net (code "86") (name "Net-(USB-D+)") (class "Default")
      (node (ref "R205") (pin "2") (pintype "passive"))
      (node (ref "R207") (pin "2") (pintype "passive"))
      (node (ref "USB") (pin "3") (pinfunction "D+_3") (pintype "passive"))
    )
    (net (code "87") (name "Net-(USB-D-)") (class "Default")
      (node (ref "R206") (pin "2") (pintype "passive"))
      (node (ref "USB") (pin "2") (pinfunction "D-_2") (pintype "passive"))
    )
    (net (code "88") (name "unconnected-(FFC1-Pad1)") (class "Default")
      (node (ref "FFC1") (pin "1") (pinfunction "1_1") (pintype "passive"))
    )
    (net (code "89") (name "unconnected-(FFC1-Pad6)") (class "Default")
      (node (ref "FFC1") (pin "6") (pinfunction "6_6") (pintype "passive"))
    )
    (net (code "90") (name "unconnected-(FFC1-Pad7)") (class "Default")
      (node (ref "FFC1") (pin "7") (pinfunction "7_7") (pintype "passive"))
    )
    (net (code "91") (name "unconnected-(U0-NC-Pad3)") (class "Default")
      (node (ref "U0") (pin "3") (pinfunction "NC_3") (pintype "passive"))
    )
    (net (code "92") (name "unconnected-(U0-NC-Pad4)") (class "Default")
      (node (ref "U0") (pin "4") (pinfunction "NC_4") (pintype "passive"))
    )
    (net (code "93") (name "unconnected-(U0-NC-Pad7)") (class "Default")
      (node (ref "U0") (pin "7") (pinfunction "NC_7") (pintype "passive"))
    )
    (net (code "94") (name "unconnected-(U0-NC-Pad10)") (class "Default")
      (node (ref "U0") (pin "10") (pinfunction "NC_10") (pintype "passive"))
    )
    (net (code "95") (name "unconnected-(U0-NC-Pad11)") (class "Default")
      (node (ref "U0") (pin "11") (pinfunction "NC_11") (pintype "passive"))
    )
    (net (code "96") (name "unconnected-(U0-NC-Pad23)") (class "Default")
      (node (ref "U0") (pin "23") (pinfunction "NC_23") (pintype "passive"))
    )
    (net (code "97") (name "unconnected-(U0-NC-Pad24)") (class "Default")
      (node (ref "U0") (pin "24") (pinfunction "NC_24") (pintype "passive"))
    )
    (net (code "98") (name "unconnected-(U0-NC-Pad25)") (class "Default")
      (node (ref "U0") (pin "25") (pinfunction "NC_25") (pintype "passive"))
    )
    (net (code "99") (name "unconnected-(U0-NC-Pad26)") (class "Default")
      (node (ref "U0") (pin "26") (pinfunction "NC_26") (pintype "passive"))
    )
    (net (code "100") (name "unconnected-(U0-NC-Pad27)") (class "Default")
      (node (ref "U0") (pin "27") (pinfunction "NC_27") (pintype "passive"))
    )
    (net (code "101") (name "unconnected-(U0-NC-Pad28)") (class "Default")
      (node (ref "U0") (pin "28") (pinfunction "NC_28") (pintype "passive"))
    )
    (net (code "102") (name "unconnected-(U2-PA0-Pad6)") (class "Default")
      (node (ref "U2") (pin "6") (pinfunction "PA0_6") (pintype "passive"))
    )
    (net (code "103") (name "unconnected-(U2-PA1-Pad7)") (class "Default")
      (node (ref "U2") (pin "7") (pinfunction "PA1_7") (pintype "passive"))
    )
    (net (code "104") (name "unconnected-(U2-PA3-Pad9)") (class "Default")
      (node (ref "U2") (pin "9") (pinfunction "PA3_9") (pintype "passive"))
    )
    (net (code "105") (name "unconnected-(U2-PA4-Pad10)") (class "Default")
      (node (ref "U2") (pin "10") (pinfunction "PA4_10") (pintype "passive"))
    )
    (net (code "106") (name "unconnected-(U2-PA8-Pad18)") (class "Default")
      (node (ref "U2") (pin "18") (pinfunction "PA8_18") (pintype "passive"))
    )
    (net (code "107") (name "unconnected-(U2-PA9-Pad19)") (class "Default")
      (node (ref "U2") (pin "19") (pinfunction "PA9_19") (pintype "passive"))
    )
    (net (code "108") (name "unconnected-(U2-PA10-Pad20)") (class "Default")
      (node (ref "U2") (pin "20") (pinfunction "PA10_20") (pintype "passive"))
    )
    (net (code "109") (name "unconnected-(U2-PA11-Pad21)") (class "Default")
      (node (ref "U2") (pin "21") (pinfunction "PA11_21") (pintype "passive"))
    )
    (net (code "110") (name "unconnected-(U2-PA12-Pad22)") (class "Default")
      (node (ref "U2") (pin "22") (pinfunction "PA12_22") (pintype "passive"))
    )
    (net (code "111") (name "unconnected-(U2-PA15-Pad25)") (class "Default")
      (node (ref "U2") (pin "25") (pinfunction "PA15_25") (pintype "passive"))
    )
    (net (code "112") (name "unconnected-(U2-PB1-Pad15)") (class "Default")
      (node (ref "U2") (pin "15") (pinfunction "PB1_15") (pintype "passive"))
    )
    (net (code "113") (name "unconnected-(U2-PB2-Pad16)") (class "Default")
      (node (ref "U2") (pin "16") (pinfunction "PB2_16") (pintype "passive"))
    )
    (net (code "114") (name "unconnected-(U2-PB3-Pad26)") (class "Default")
      (node (ref "U2") (pin "26") (pinfunction "PB3_26") (pintype "passive"))
    )
    (net (code "115") (name "unconnected-(U2-PB4-Pad27)") (class "Default")
      (node (ref "U2") (pin "27") (pinfunction "PB4_27") (pintype "passive"))
    )
    (net (code "116") (name "unconnected-(U2-PB5-Pad28)") (class "Default")
      (node (ref "U2") (pin "28") (pinfunction "PB5_28") (pintype "passive"))
    )
    (net (code "117") (name "unconnected-(U2-PB6-Pad29)") (class "Default")
      (node (ref "U2") (pin "29") (pinfunction "PB6_29") (pintype "passive"))
    )
    (net (code "118") (name "unconnected-(U2-PB7-Pad30)") (class "Default")
      (node (ref "U2") (pin "30") (pinfunction "PB7_30") (pintype "passive"))
    )
    (net (code "119") (name "unconnected-(U2-PB8-Pad32)") (class "Default")
      (node (ref "U2") (pin "32") (pinfunction "PB8_32") (pintype "passive"))
    )
    (net (code "120") (name "unconnected-(U2-PF0-Pad2)") (class "Default")
      (node (ref "U2") (pin "2") (pinfunction "PF0_2") (pintype "passive"))
    )
    (net (code "121") (name "unconnected-(U2-PF1-Pad3)") (class "Default")
      (node (ref "U2") (pin "3") (pinfunction "PF1_3") (pintype "passive"))
    )
    (net (code "122") (name "unconnected-(U5-PA1-Pad15)") (class "Default")
      (node (ref "U5") (pin "15") (pinfunction "PA1_15") (pintype "bidirectional"))
    )
    (net (code "123") (name "unconnected-(U5-PA2-Pad16)") (class "Default")
      (node (ref "U5") (pin "16") (pinfunction "PA2_16") (pintype "bidirectional"))
    )
    (net (code "124") (name "unconnected-(U5-PA3-Pad17)") (class "Default")
      (node (ref "U5") (pin "17") (pinfunction "PA3_17") (pintype "bidirectional"))
    )
    (net (code "125") (name "unconnected-(U5-PA8-Pad41)") (class "Default")
      (node (ref "U5") (pin "41") (pinfunction "PA8_41") (pintype "bidirectional"))
    )
    (net (code "126") (name "unconnected-(U5-PA15{slash}JTDI-Pad50)") (class "Default")
      (node (ref "U5") (pin "50") (pinfunction "PA15/JTDI_50") (pintype "bidirectional"))
    )
    (net (code "127") (name "unconnected-(U5-PB0-Pad26)") (class "Default")
      (node (ref "U5") (pin "26") (pinfunction "PB0_26") (pintype "bidirectional"))
    )
    (net (code "128") (name "unconnected-(U5-PB1-Pad27)") (class "Default")
      (node (ref "U5") (pin "27") (pinfunction "PB1_27") (pintype "bidirectional"))
    )
    (net (code "129") (name "unconnected-(U5-PB2{slash}BOOT1-Pad28)") (class "Default")
      (node (ref "U5") (pin "28") (pinfunction "PB2/BOOT1_28") (pintype "bidirectional"))
    )
    (net (code "130") (name "unconnected-(U5-PB3{slash}JTDO-Pad55)") (class "Default")
      (node (ref "U5") (pin "55") (pinfunction "PB3/JTDO_55") (pintype "bidirectional"))
    )
    (net (code "131") (name "unconnected-(U5-PB4{slash}JNTRST-Pad56)") (class "Default")
      (node (ref "U5") (pin "56") (pinfunction "PB4/JNTRST_56") (pintype "bidirectional"))
    )
    (net (code "132") (name "unconnected-(U5-PB5-Pad57)") (class "Default")
      (node (ref "U5") (pin "57") (pinfunction "PB5_57") (pintype "bidirectional"))
    )
    (net (code "133") (name "unconnected-(U5-PB6-Pad58)") (class "Default")
      (node (ref "U5") (pin "58") (pinfunction "PB6_58") (pintype "bidirectional"))
    )
    (net (code "134") (name "unconnected-(U5-PB7-Pad59)") (class "Default")
      (node (ref "U5") (pin "59") (pinfunction "PB7_59") (pintype "bidirectional"))
    )
    (net (code "135") (name "unconnected-(U5-PB8-Pad61)") (class "Default")
      (node (ref "U5") (pin "61") (pinfunction "PB8_61") (pintype "bidirectional"))
    )
    (net (code "136") (name "unconnected-(U5-PB9-Pad62)") (class "Default")
      (node (ref "U5") (pin "62") (pinfunction "PB9_62") (pintype "bidirectional"))
    )
    (net (code "137") (name "unconnected-(U5-PC6-Pad37)") (class "Default")
      (node (ref "U5") (pin "37") (pinfunction "PC6_37") (pintype "bidirectional"))
    )
    (net (code "138") (name "unconnected-(U5-PC7-Pad38)") (class "Default")
      (node (ref "U5") (pin "38") (pinfunction "PC7_38") (pintype "bidirectional"))
    )
    (net (code "139") (name "unconnected-(U5-PC8-Pad39)") (class "Default")
      (node (ref "U5") (pin "39") (pinfunction "PC8_39") (pintype "bidirectional"))
    )
    (net (code "140") (name "unconnected-(U5-PC9-Pad40)") (class "Default")
      (node (ref "U5") (pin "40") (pinfunction "PC9_40") (pintype "bidirectional"))
    )
    (net (code "141") (name "unconnected-(U5-PC11-Pad52)") (class "Default")
      (node (ref "U5") (pin "52") (pinfunction "PC11_52") (pintype "bidirectional"))
    )
    (net (code "142") (name "unconnected-(U5-PC12-Pad53)") (class "Default")
      (node (ref "U5") (pin "53") (pinfunction "PC12_53") (pintype "bidirectional"))
    )
    (net (code "143") (name "unconnected-(U5-PC14-OSC32_IN-Pad3)") (class "Default")
      (node (ref "U5") (pin "3") (pinfunction "PC14-OSC32_IN_3") (pintype "bidirectional"))
    )
    (net (code "144") (name "unconnected-(U5-PC15-OSC32_OUT-Pad4)") (class "Default")
      (node (ref "U5") (pin "4") (pinfunction "PC15-OSC32_OUT_4") (pintype "bidirectional"))
    )
    (net (code "145") (name "unconnected-(U5-PD2-Pad54)") (class "Default")
      (node (ref "U5") (pin "54") (pinfunction "PD2_54") (pintype "bidirectional"))
    )
    (net (code "146") (name "unconnected-(USB-NC-Pad4)") (class "Default")
      (node (ref "USB") (pin "4") (pinfunction "NC_4") (pintype "passive"))
    )
  )
)
